# Top.net
KiCad netlist of a schematic drawn in EAGLE
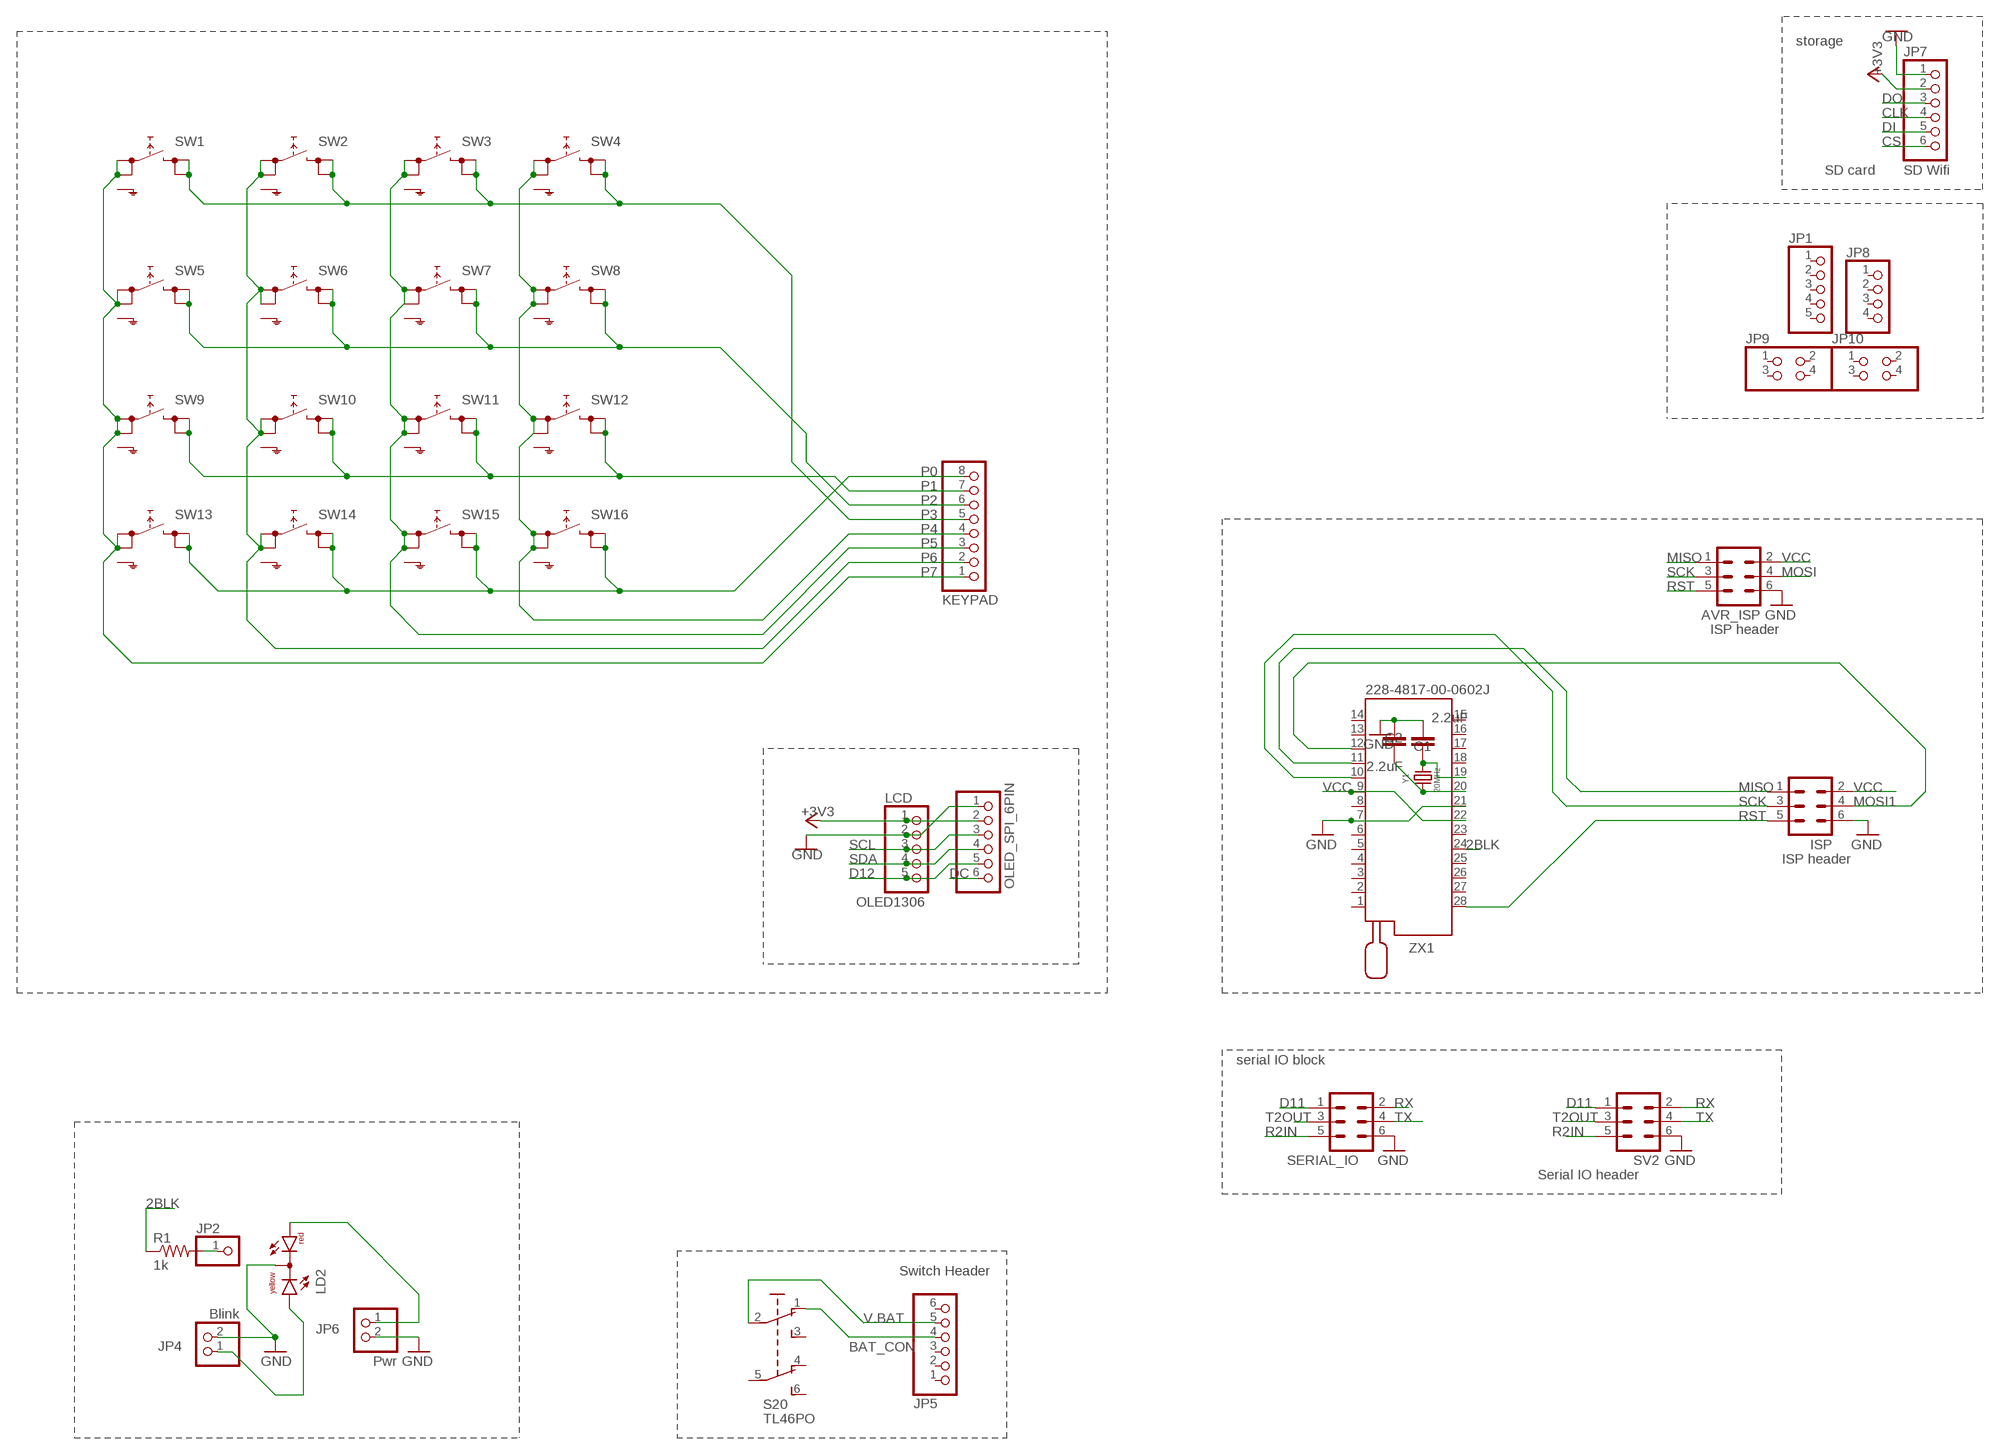
[diagram p0: schematic, sheet 1]

(export (version "E")
  (design (tool "Eeschema 10.0.6"))
  (components
    (comp (ref "AVR_ISP")
      (value "ML6")
      (footprint "eagle-import:ML6")
      (libsource (lib "eagle-import") (part "ML6"))
    )
    (comp (ref "C1")
      (value "2.2uF")
      (footprint "eagle-import:1206")
      (libsource (lib "eagle-import") (part "2.2UF-1206-50V-10%"))
    )
    (comp (ref "C2")
      (value "2.2uF")
      (footprint "eagle-import:1206")
      (libsource (lib "eagle-import") (part "2.2UF-1206-50V-10%"))
    )
    (comp (ref "ISP")
      (value "ML6")
      (footprint "eagle-import:ML6")
      (libsource (lib "eagle-import") (part "ML6"))
    )
    (comp (ref "JP1")
      (value "PINHD-1X5")
      (footprint "eagle-import:1X05")
      (libsource (lib "eagle-import") (part "PINHD-1X5"))
    )
    (comp (ref "JP2")
      (value "PINHD-1X1")
      (footprint "eagle-import:1X01")
      (libsource (lib "eagle-import") (part "PINHD-1X1"))
    )
    (comp (ref "JP4")
      (value "Blink")
      (footprint "eagle-import:1X02")
      (libsource (lib "eagle-import") (part "PINHD-1X2"))
    )
    (comp (ref "JP5")
      (value "Switch Header")
      (footprint "eagle-import:1X06")
      (libsource (lib "eagle-import") (part "pinhead_325_PINHD-1X6"))
    )
    (comp (ref "JP6")
      (value "Pwr")
      (footprint "eagle-import:1X02")
      (libsource (lib "eagle-import") (part "PINHD-1X2"))
    )
    (comp (ref "JP7")
      (value "SD Wifi")
      (footprint "eagle-import:1X06")
      (libsource (lib "eagle-import") (part "pinhead_325_PINHD-1X6"))
    )
    (comp (ref "JP8")
      (value "PINHD-1X4")
      (footprint "eagle-import:1X04")
      (libsource (lib "eagle-import") (part "PINHD-1X4"))
    )
    (comp (ref "JP9")
      (value "PINHD-2X2")
      (footprint "eagle-import:2X02")
      (libsource (lib "eagle-import") (part "PINHD-2X2"))
    )
    (comp (ref "JP10")
      (value "PINHD-2X2")
      (footprint "eagle-import:2X02")
      (libsource (lib "eagle-import") (part "PINHD-2X2"))
    )
    (comp (ref "KEYPAD")
      (value "PINHD-1X8")
      (footprint "eagle-import:1X08")
      (libsource (lib "eagle-import") (part "PINHD-1X8"))
    )
    (comp (ref "LCD")
      (value "OLED1306")
      (footprint "eagle-import:1X05")
      (libsource (lib "eagle-import") (part "PINHD-1X5"))
    )
    (comp (ref "LD2")
      (value "DUOLED-RY-C")
      (footprint "eagle-import:DUOLED-C-5MM")
      (libsource (lib "eagle-import") (part "DUOLED-RY-C"))
    )
    (comp (ref "OLED_SPI_6PIN")
      (value "PINHD-1X6")
      (footprint "eagle-import:1X06")
      (libsource (lib "eagle-import") (part "PINHD-1X6"))
    )
    (comp (ref "R1")
      (value "1k")
      (footprint "eagle-import:M1206")
      (libsource (lib "eagle-import") (part "R-US_M1206"))
    )
    (comp (ref "S20")
      (value "TL46PO")
      (footprint "eagle-import:TL4XPO")
      (libsource (lib "eagle-import") (part "TL46PO"))
    )
    (comp (ref "SERIAL_IO")
      (value "ML6")
      (footprint "eagle-import:ML6")
      (libsource (lib "eagle-import") (part "ML6"))
    )
    (comp (ref "SV2")
      (value "ML6")
      (footprint "eagle-import:ML6")
      (libsource (lib "eagle-import") (part "ML6"))
    )
    (comp (ref "SW1")
      (value "SKHMPSE010")
      (footprint "eagle-import:SKHMPXE010")
      (libsource (lib "eagle-import") (part "SKHMPE010S"))
    )
    (comp (ref "SW2")
      (value "SKHMPSE010")
      (footprint "eagle-import:SKHMPXE010")
      (libsource (lib "eagle-import") (part "SKHMPE010S"))
    )
    (comp (ref "SW3")
      (value "SKHMPSE010")
      (footprint "eagle-import:SKHMPXE010")
      (libsource (lib "eagle-import") (part "SKHMPE010S"))
    )
    (comp (ref "SW4")
      (value "SKHMPSE010")
      (footprint "eagle-import:SKHMPXE010")
      (libsource (lib "eagle-import") (part "SKHMPE010S"))
    )
    (comp (ref "SW5")
      (value "SKHMPSE010")
      (footprint "eagle-import:SKHMPXE010")
      (libsource (lib "eagle-import") (part "SKHMPE010S"))
    )
    (comp (ref "SW6")
      (value "SKHMPSE010")
      (footprint "eagle-import:SKHMPXE010")
      (libsource (lib "eagle-import") (part "SKHMPE010S"))
    )
    (comp (ref "SW7")
      (value "SKHMPSE010")
      (footprint "eagle-import:SKHMPXE010")
      (libsource (lib "eagle-import") (part "SKHMPE010S"))
    )
    (comp (ref "SW8")
      (value "SKHMPSE010")
      (footprint "eagle-import:SKHMPXE010")
      (libsource (lib "eagle-import") (part "SKHMPE010S"))
    )
    (comp (ref "SW9")
      (value "SKHMPSE010")
      (footprint "eagle-import:SKHMPXE010")
      (libsource (lib "eagle-import") (part "SKHMPE010S"))
    )
    (comp (ref "SW10")
      (value "SKHMPSE010")
      (footprint "eagle-import:SKHMPXE010")
      (libsource (lib "eagle-import") (part "SKHMPE010S"))
    )
    (comp (ref "SW11")
      (value "SKHMPSE010")
      (footprint "eagle-import:SKHMPXE010")
      (libsource (lib "eagle-import") (part "SKHMPE010S"))
    )
    (comp (ref "SW12")
      (value "SKHMPSE010")
      (footprint "eagle-import:SKHMPXE010")
      (libsource (lib "eagle-import") (part "SKHMPE010S"))
    )
    (comp (ref "SW13")
      (value "SKHMPSE010")
      (footprint "eagle-import:SKHMPXE010")
      (libsource (lib "eagle-import") (part "SKHMPE010S"))
    )
    (comp (ref "SW14")
      (value "SKHMPSE010")
      (footprint "eagle-import:SKHMPXE010")
      (libsource (lib "eagle-import") (part "SKHMPE010S"))
    )
    (comp (ref "SW15")
      (value "SKHMPSE010")
      (footprint "eagle-import:SKHMPXE010")
      (libsource (lib "eagle-import") (part "SKHMPE010S"))
    )
    (comp (ref "SW16")
      (value "SKHMPSE010")
      (footprint "eagle-import:SKHMPXE010")
      (libsource (lib "eagle-import") (part "SKHMPE010S"))
    )
    (comp (ref "Y1")
      (value "20MHz")
      (footprint "eagle-import:WE-XTAL_HC49_4HSMX")
      (fields (field (name "TOLERANCE") "±10ppm"))
      (libsource (lib "eagle-import") (part "WE-XTAL_HC49/4HSMX_830061856"))
    )
    (comp (ref "ZX1")
      (value "228-4817-00-0602J")
      (footprint "eagle-import:228-4817-00-0602J")
      (fields (field (name "MF") "3M"))
      (libsource (lib "eagle-import") (part "228-?00-0602J4817-"))
    )
  )
  (nets
    (net (code "1") (name "+3V3") (class "Default")
      (node (ref "JP7") (pin "2") (pinfunction "2_2") (pintype "passive"))
      (node (ref "LCD") (pin "1") (pinfunction "1_1") (pintype "passive"))
      (node (ref "OLED_SPI_6PIN") (pin "2") (pinfunction "2_2") (pintype "passive"))
    )
    (net (code "2") (name "/2BLK") (class "Default")
      (node (ref "R1") (pin "1") (pinfunction "1_1") (pintype "passive"))
      (node (ref "ZX1") (pin "24") (pinfunction "24_24") (pintype "passive"))
    )
    (net (code "3") (name "/BAT_CON") (class "Default")
      (node (ref "JP5") (pin "4") (pinfunction "4_4") (pintype "passive"))
      (node (ref "S20") (pin "1") (pinfunction "O_1") (pintype "passive"))
    )
    (net (code "4") (name "/CLK") (class "Default")
      (node (ref "JP7") (pin "4") (pinfunction "4_4") (pintype "passive"))
    )
    (net (code "5") (name "/CS") (class "Default")
      (node (ref "JP7") (pin "6") (pinfunction "6_6") (pintype "passive"))
    )
    (net (code "6") (name "/D11") (class "Default")
      (node (ref "SERIAL_IO") (pin "1") (pinfunction "1_1") (pintype "passive"))
      (node (ref "SV2") (pin "1") (pinfunction "1_1") (pintype "passive"))
    )
    (net (code "7") (name "/D12") (class "Default")
      (node (ref "LCD") (pin "5") (pinfunction "5_5") (pintype "passive"))
      (node (ref "OLED_SPI_6PIN") (pin "5") (pinfunction "5_5") (pintype "passive"))
    )
    (net (code "8") (name "/DC") (class "Default")
      (node (ref "OLED_SPI_6PIN") (pin "6") (pinfunction "6_6") (pintype "passive"))
    )
    (net (code "9") (name "/DI") (class "Default")
      (node (ref "JP7") (pin "5") (pinfunction "5_5") (pintype "passive"))
    )
    (net (code "10") (name "/DO") (class "Default")
      (node (ref "JP7") (pin "3") (pinfunction "3_3") (pintype "passive"))
    )
    (net (code "11") (name "/MISO") (class "Default")
      (node (ref "AVR_ISP") (pin "1") (pinfunction "1_1") (pintype "passive"))
      (node (ref "ISP") (pin "1") (pinfunction "1_1") (pintype "passive"))
      (node (ref "ZX1") (pin "11") (pinfunction "11_11") (pintype "passive"))
    )
    (net (code "12") (name "/MOSI") (class "Default")
      (node (ref "AVR_ISP") (pin "4") (pinfunction "4_4") (pintype "passive"))
    )
    (net (code "13") (name "/MOSI1") (class "Default")
      (node (ref "ISP") (pin "4") (pinfunction "4_4") (pintype "passive"))
      (node (ref "ZX1") (pin "12") (pinfunction "12_12") (pintype "passive"))
    )
    (net (code "14") (name "/P0") (class "Default")
      (node (ref "KEYPAD") (pin "8") (pinfunction "8_8") (pintype "passive"))
      (node (ref "SW13") (pin "3") (pinfunction "2.1_3") (pintype "passive"))
      (node (ref "SW13") (pin "4") (pinfunction "2.2_4") (pintype "passive"))
      (node (ref "SW14") (pin "3") (pinfunction "2.1_3") (pintype "passive"))
      (node (ref "SW14") (pin "4") (pinfunction "2.2_4") (pintype "passive"))
      (node (ref "SW15") (pin "3") (pinfunction "2.1_3") (pintype "passive"))
      (node (ref "SW15") (pin "4") (pinfunction "2.2_4") (pintype "passive"))
      (node (ref "SW16") (pin "3") (pinfunction "2.1_3") (pintype "passive"))
      (node (ref "SW16") (pin "4") (pinfunction "2.2_4") (pintype "passive"))
    )
    (net (code "15") (name "/P1") (class "Default")
      (node (ref "KEYPAD") (pin "7") (pinfunction "7_7") (pintype "passive"))
      (node (ref "SW10") (pin "3") (pinfunction "2.1_3") (pintype "passive"))
      (node (ref "SW10") (pin "4") (pinfunction "2.2_4") (pintype "passive"))
      (node (ref "SW11") (pin "3") (pinfunction "2.1_3") (pintype "passive"))
      (node (ref "SW11") (pin "4") (pinfunction "2.2_4") (pintype "passive"))
      (node (ref "SW12") (pin "3") (pinfunction "2.1_3") (pintype "passive"))
      (node (ref "SW12") (pin "4") (pinfunction "2.2_4") (pintype "passive"))
      (node (ref "SW9") (pin "3") (pinfunction "2.1_3") (pintype "passive"))
      (node (ref "SW9") (pin "4") (pinfunction "2.2_4") (pintype "passive"))
    )
    (net (code "16") (name "/P2") (class "Default")
      (node (ref "KEYPAD") (pin "6") (pinfunction "6_6") (pintype "passive"))
      (node (ref "SW5") (pin "3") (pinfunction "2.1_3") (pintype "passive"))
      (node (ref "SW5") (pin "4") (pinfunction "2.2_4") (pintype "passive"))
      (node (ref "SW6") (pin "3") (pinfunction "2.1_3") (pintype "passive"))
      (node (ref "SW6") (pin "4") (pinfunction "2.2_4") (pintype "passive"))
      (node (ref "SW7") (pin "3") (pinfunction "2.1_3") (pintype "passive"))
      (node (ref "SW7") (pin "4") (pinfunction "2.2_4") (pintype "passive"))
      (node (ref "SW8") (pin "3") (pinfunction "2.1_3") (pintype "passive"))
      (node (ref "SW8") (pin "4") (pinfunction "2.2_4") (pintype "passive"))
    )
    (net (code "17") (name "/P3") (class "Default")
      (node (ref "KEYPAD") (pin "5") (pinfunction "5_5") (pintype "passive"))
      (node (ref "SW1") (pin "3") (pinfunction "2.1_3") (pintype "passive"))
      (node (ref "SW1") (pin "4") (pinfunction "2.2_4") (pintype "passive"))
      (node (ref "SW2") (pin "3") (pinfunction "2.1_3") (pintype "passive"))
      (node (ref "SW2") (pin "4") (pinfunction "2.2_4") (pintype "passive"))
      (node (ref "SW3") (pin "3") (pinfunction "2.1_3") (pintype "passive"))
      (node (ref "SW3") (pin "4") (pinfunction "2.2_4") (pintype "passive"))
      (node (ref "SW4") (pin "3") (pinfunction "2.1_3") (pintype "passive"))
      (node (ref "SW4") (pin "4") (pinfunction "2.2_4") (pintype "passive"))
    )
    (net (code "18") (name "/P4") (class "Default")
      (node (ref "KEYPAD") (pin "4") (pinfunction "4_4") (pintype "passive"))
      (node (ref "SW12") (pin "1") (pinfunction "1.1_1") (pintype "passive"))
      (node (ref "SW12") (pin "2") (pinfunction "1.2_2") (pintype "passive"))
      (node (ref "SW16") (pin "1") (pinfunction "1.1_1") (pintype "passive"))
      (node (ref "SW16") (pin "2") (pinfunction "1.2_2") (pintype "passive"))
      (node (ref "SW4") (pin "1") (pinfunction "1.1_1") (pintype "passive"))
      (node (ref "SW4") (pin "2") (pinfunction "1.2_2") (pintype "passive"))
      (node (ref "SW8") (pin "1") (pinfunction "1.1_1") (pintype "passive"))
      (node (ref "SW8") (pin "2") (pinfunction "1.2_2") (pintype "passive"))
    )
    (net (code "19") (name "/P5") (class "Default")
      (node (ref "KEYPAD") (pin "3") (pinfunction "3_3") (pintype "passive"))
      (node (ref "SW11") (pin "1") (pinfunction "1.1_1") (pintype "passive"))
      (node (ref "SW11") (pin "2") (pinfunction "1.2_2") (pintype "passive"))
      (node (ref "SW15") (pin "1") (pinfunction "1.1_1") (pintype "passive"))
      (node (ref "SW15") (pin "2") (pinfunction "1.2_2") (pintype "passive"))
      (node (ref "SW3") (pin "1") (pinfunction "1.1_1") (pintype "passive"))
      (node (ref "SW3") (pin "2") (pinfunction "1.2_2") (pintype "passive"))
      (node (ref "SW7") (pin "1") (pinfunction "1.1_1") (pintype "passive"))
      (node (ref "SW7") (pin "2") (pinfunction "1.2_2") (pintype "passive"))
    )
    (net (code "20") (name "/P6") (class "Default")
      (node (ref "KEYPAD") (pin "2") (pinfunction "2_2") (pintype "passive"))
      (node (ref "SW10") (pin "1") (pinfunction "1.1_1") (pintype "passive"))
      (node (ref "SW10") (pin "2") (pinfunction "1.2_2") (pintype "passive"))
      (node (ref "SW14") (pin "1") (pinfunction "1.1_1") (pintype "passive"))
      (node (ref "SW14") (pin "2") (pinfunction "1.2_2") (pintype "passive"))
      (node (ref "SW2") (pin "1") (pinfunction "1.1_1") (pintype "passive"))
      (node (ref "SW2") (pin "2") (pinfunction "1.2_2") (pintype "passive"))
      (node (ref "SW6") (pin "1") (pinfunction "1.1_1") (pintype "passive"))
      (node (ref "SW6") (pin "2") (pinfunction "1.2_2") (pintype "passive"))
    )
    (net (code "21") (name "/P7") (class "Default")
      (node (ref "KEYPAD") (pin "1") (pinfunction "1_1") (pintype "passive"))
      (node (ref "SW1") (pin "1") (pinfunction "1.1_1") (pintype "passive"))
      (node (ref "SW1") (pin "2") (pinfunction "1.2_2") (pintype "passive"))
      (node (ref "SW13") (pin "1") (pinfunction "1.1_1") (pintype "passive"))
      (node (ref "SW13") (pin "2") (pinfunction "1.2_2") (pintype "passive"))
      (node (ref "SW5") (pin "1") (pinfunction "1.1_1") (pintype "passive"))
      (node (ref "SW5") (pin "2") (pinfunction "1.2_2") (pintype "passive"))
      (node (ref "SW9") (pin "1") (pinfunction "1.1_1") (pintype "passive"))
      (node (ref "SW9") (pin "2") (pinfunction "1.2_2") (pintype "passive"))
    )
    (net (code "22") (name "/R2IN") (class "Default")
      (node (ref "SERIAL_IO") (pin "5") (pinfunction "5_5") (pintype "passive"))
      (node (ref "SV2") (pin "5") (pinfunction "5_5") (pintype "passive"))
    )
    (net (code "23") (name "/RST") (class "Default")
      (node (ref "AVR_ISP") (pin "5") (pinfunction "5_5") (pintype "passive"))
      (node (ref "ISP") (pin "5") (pinfunction "5_5") (pintype "passive"))
      (node (ref "ZX1") (pin "28") (pinfunction "28_28") (pintype "passive"))
    )
    (net (code "24") (name "/RX") (class "Default")
      (node (ref "SERIAL_IO") (pin "2") (pinfunction "2_2") (pintype "passive"))
      (node (ref "SV2") (pin "2") (pinfunction "2_2") (pintype "passive"))
    )
    (net (code "25") (name "/SCK") (class "Default")
      (node (ref "AVR_ISP") (pin "3") (pinfunction "3_3") (pintype "passive"))
      (node (ref "ISP") (pin "3") (pinfunction "3_3") (pintype "passive"))
      (node (ref "ZX1") (pin "10") (pinfunction "10_10") (pintype "passive"))
    )
    (net (code "26") (name "/SCL") (class "Default")
      (node (ref "LCD") (pin "3") (pinfunction "3_3") (pintype "passive"))
      (node (ref "OLED_SPI_6PIN") (pin "3") (pinfunction "3_3") (pintype "passive"))
    )
    (net (code "27") (name "/SDA") (class "Default")
      (node (ref "LCD") (pin "4") (pinfunction "4_4") (pintype "passive"))
      (node (ref "OLED_SPI_6PIN") (pin "4") (pinfunction "4_4") (pintype "passive"))
    )
    (net (code "28") (name "/T2OUT") (class "Default")
      (node (ref "SERIAL_IO") (pin "3") (pinfunction "3_3") (pintype "passive"))
      (node (ref "SV2") (pin "3") (pinfunction "3_3") (pintype "passive"))
    )
    (net (code "29") (name "/TX") (class "Default")
      (node (ref "SERIAL_IO") (pin "4") (pinfunction "4_4") (pintype "passive"))
      (node (ref "SV2") (pin "4") (pinfunction "4_4") (pintype "passive"))
    )
    (net (code "30") (name "/V.BAT") (class "Default")
      (node (ref "JP5") (pin "5") (pinfunction "5_5") (pintype "passive"))
      (node (ref "S20") (pin "2") (pinfunction "P_2") (pintype "passive"))
    )
    (net (code "31") (name "/VCC") (class "Default")
      (node (ref "AVR_ISP") (pin "2") (pinfunction "2_2") (pintype "passive"))
      (node (ref "ISP") (pin "2") (pinfunction "2_2") (pintype "passive"))
      (node (ref "ZX1") (pin "22") (pinfunction "22_22") (pintype "passive"))
      (node (ref "ZX1") (pin "9") (pinfunction "9_9") (pintype "passive"))
    )
    (net (code "32") (name "GND") (class "Default")
      (node (ref "AVR_ISP") (pin "6") (pinfunction "6_6") (pintype "passive"))
      (node (ref "C1") (pin "2") (pinfunction "2_2") (pintype "passive"))
      (node (ref "C2") (pin "1") (pinfunction "1_1") (pintype "passive"))
      (node (ref "ISP") (pin "6") (pinfunction "6_6") (pintype "passive"))
      (node (ref "JP4") (pin "2") (pinfunction "2_2") (pintype "passive"))
      (node (ref "JP6") (pin "2") (pinfunction "2_2") (pintype "passive"))
      (node (ref "JP7") (pin "1") (pinfunction "1_1") (pintype "passive"))
      (node (ref "LCD") (pin "2") (pinfunction "2_2") (pintype "passive"))
      (node (ref "LD2") (pin "C") (pinfunction "C_C") (pintype "passive"))
      (node (ref "OLED_SPI_6PIN") (pin "1") (pinfunction "1_1") (pintype "passive"))
      (node (ref "SERIAL_IO") (pin "6") (pinfunction "6_6") (pintype "passive"))
      (node (ref "SV2") (pin "6") (pinfunction "6_6") (pintype "passive"))
      (node (ref "ZX1") (pin "21") (pinfunction "21_21") (pintype "passive"))
      (node (ref "ZX1") (pin "7") (pinfunction "7_7") (pintype "passive"))
    )
    (net (code "33") (name "Net-(C1-Pad1)") (class "Default")
      (node (ref "C1") (pin "1") (pinfunction "1_1") (pintype "passive"))
      (node (ref "Y1") (pin "2") (pinfunction "2_2") (pintype "passive"))
      (node (ref "ZX1") (pin "19") (pinfunction "19_19") (pintype "passive"))
    )
    (net (code "34") (name "Net-(C2-Pad2)") (class "Default")
      (node (ref "C2") (pin "2") (pinfunction "2_2") (pintype "passive"))
      (node (ref "Y1") (pin "1") (pinfunction "1_1") (pintype "passive"))
      (node (ref "ZX1") (pin "20") (pinfunction "20_20") (pintype "passive"))
    )
    (net (code "35") (name "Net-(JP2-Pad1)") (class "Default")
      (node (ref "JP2") (pin "1") (pinfunction "1_1") (pintype "passive"))
      (node (ref "R1") (pin "2") (pinfunction "2_2") (pintype "passive"))
    )
    (net (code "36") (name "Net-(JP6-Pad1)") (class "Default")
      (node (ref "JP6") (pin "1") (pinfunction "1_1") (pintype "passive"))
      (node (ref "LD2") (pin "AR") (pinfunction "AR_AR") (pintype "passive"))
    )
    (net (code "37") (name "Net-(LD2-AY)") (class "Default")
      (node (ref "JP4") (pin "1") (pinfunction "1_1") (pintype "passive"))
      (node (ref "LD2") (pin "AX") (pinfunction "AY_AX") (pintype "passive"))
    )
    (net (code "38") (name "unconnected-(JP1-Pad1)") (class "Default")
      (node (ref "JP1") (pin "1") (pinfunction "1_1") (pintype "passive"))
    )
    (net (code "39") (name "unconnected-(JP1-Pad2)") (class "Default")
      (node (ref "JP1") (pin "2") (pinfunction "2_2") (pintype "passive"))
    )
    (net (code "40") (name "unconnected-(JP1-Pad3)") (class "Default")
      (node (ref "JP1") (pin "3") (pinfunction "3_3") (pintype "passive"))
    )
    (net (code "41") (name "unconnected-(JP1-Pad4)") (class "Default")
      (node (ref "JP1") (pin "4") (pinfunction "4_4") (pintype "passive"))
    )
    (net (code "42") (name "unconnected-(JP1-Pad5)") (class "Default")
      (node (ref "JP1") (pin "5") (pinfunction "5_5") (pintype "passive"))
    )
    (net (code "43") (name "unconnected-(JP5-Pad1)") (class "Default")
      (node (ref "JP5") (pin "1") (pinfunction "1_1") (pintype "passive"))
    )
    (net (code "44") (name "unconnected-(JP5-Pad2)") (class "Default")
      (node (ref "JP5") (pin "2") (pinfunction "2_2") (pintype "passive"))
    )
    (net (code "45") (name "unconnected-(JP5-Pad3)") (class "Default")
      (node (ref "JP5") (pin "3") (pinfunction "3_3") (pintype "passive"))
    )
    (net (code "46") (name "unconnected-(JP5-Pad6)") (class "Default")
      (node (ref "JP5") (pin "6") (pinfunction "6_6") (pintype "passive"))
    )
    (net (code "47") (name "unconnected-(JP8-Pad1)") (class "Default")
      (node (ref "JP8") (pin "1") (pinfunction "1_1") (pintype "passive"))
    )
    (net (code "48") (name "unconnected-(JP8-Pad2)") (class "Default")
      (node (ref "JP8") (pin "2") (pinfunction "2_2") (pintype "passive"))
    )
    (net (code "49") (name "unconnected-(JP8-Pad3)") (class "Default")
      (node (ref "JP8") (pin "3") (pinfunction "3_3") (pintype "passive"))
    )
    (net (code "50") (name "unconnected-(JP8-Pad4)") (class "Default")
      (node (ref "JP8") (pin "4") (pinfunction "4_4") (pintype "passive"))
    )
    (net (code "51") (name "unconnected-(JP9-Pad1)") (class "Default")
      (node (ref "JP9") (pin "1") (pinfunction "1_1") (pintype "passive"))
    )
    (net (code "52") (name "unconnected-(JP9-Pad2)") (class "Default")
      (node (ref "JP9") (pin "2") (pinfunction "2_2") (pintype "passive"))
    )
    (net (code "53") (name "unconnected-(JP9-Pad3)") (class "Default")
      (node (ref "JP9") (pin "3") (pinfunction "3_3") (pintype "passive"))
    )
    (net (code "54") (name "unconnected-(JP9-Pad4)") (class "Default")
      (node (ref "JP9") (pin "4") (pinfunction "4_4") (pintype "passive"))
    )
    (net (code "55") (name "unconnected-(JP10-Pad1)") (class "Default")
      (node (ref "JP10") (pin "1") (pinfunction "1_1") (pintype "passive"))
    )
    (net (code "56") (name "unconnected-(JP10-Pad2)") (class "Default")
      (node (ref "JP10") (pin "2") (pinfunction "2_2") (pintype "passive"))
    )
    (net (code "57") (name "unconnected-(JP10-Pad3)") (class "Default")
      (node (ref "JP10") (pin "3") (pinfunction "3_3") (pintype "passive"))
    )
    (net (code "58") (name "unconnected-(JP10-Pad4)") (class "Default")
      (node (ref "JP10") (pin "4") (pinfunction "4_4") (pintype "passive"))
    )
    (net (code "59") (name "unconnected-(S20-O1-Pad4)") (class "Default")
      (node (ref "S20") (pin "4") (pinfunction "O1_4") (pintype "passive"))
    )
    (net (code "60") (name "unconnected-(S20-P1-Pad5)") (class "Default")
      (node (ref "S20") (pin "5") (pinfunction "P1_5") (pintype "passive"))
    )
    (net (code "61") (name "unconnected-(S20-S-Pad3)") (class "Default")
      (node (ref "S20") (pin "3") (pinfunction "S_3") (pintype "passive"))
    )
    (net (code "62") (name "unconnected-(S20-S1-Pad6)") (class "Default")
      (node (ref "S20") (pin "6") (pinfunction "S1_6") (pintype "passive"))
    )
    (net (code "63") (name "unconnected-(SW1-SH-Pad5)") (class "Default")
      (node (ref "SW1") (pin "5") (pinfunction "SH_5") (pintype "passive"))
    )
    (net (code "64") (name "unconnected-(SW2-SH-Pad5)") (class "Default")
      (node (ref "SW2") (pin "5") (pinfunction "SH_5") (pintype "passive"))
    )
    (net (code "65") (name "unconnected-(SW3-SH-Pad5)") (class "Default")
      (node (ref "SW3") (pin "5") (pinfunction "SH_5") (pintype "passive"))
    )
    (net (code "66") (name "unconnected-(SW4-SH-Pad5)") (class "Default")
      (node (ref "SW4") (pin "5") (pinfunction "SH_5") (pintype "passive"))
    )
    (net (code "67") (name "unconnected-(SW5-SH-Pad5)") (class "Default")
      (node (ref "SW5") (pin "5") (pinfunction "SH_5") (pintype "passive"))
    )
    (net (code "68") (name "unconnected-(SW6-SH-Pad5)") (class "Default")
      (node (ref "SW6") (pin "5") (pinfunction "SH_5") (pintype "passive"))
    )
    (net (code "69") (name "unconnected-(SW7-SH-Pad5)") (class "Default")
      (node (ref "SW7") (pin "5") (pinfunction "SH_5") (pintype "passive"))
    )
    (net (code "70") (name "unconnected-(SW8-SH-Pad5)") (class "Default")
      (node (ref "SW8") (pin "5") (pinfunction "SH_5") (pintype "passive"))
    )
    (net (code "71") (name "unconnected-(SW9-SH-Pad5)") (class "Default")
      (node (ref "SW9") (pin "5") (pinfunction "SH_5") (pintype "passive"))
    )
    (net (code "72") (name "unconnected-(SW10-SH-Pad5)") (class "Default")
      (node (ref "SW10") (pin "5") (pinfunction "SH_5") (pintype "passive"))
    )
    (net (code "73") (name "unconnected-(SW11-SH-Pad5)") (class "Default")
      (node (ref "SW11") (pin "5") (pinfunction "SH_5") (pintype "passive"))
    )
    (net (code "74") (name "unconnected-(SW12-SH-Pad5)") (class "Default")
      (node (ref "SW12") (pin "5") (pinfunction "SH_5") (pintype "passive"))
    )
    (net (code "75") (name "unconnected-(SW13-SH-Pad5)") (class "Default")
      (node (ref "SW13") (pin "5") (pinfunction "SH_5") (pintype "passive"))
    )
    (net (code "76") (name "unconnected-(SW14-SH-Pad5)") (class "Default")
      (node (ref "SW14") (pin "5") (pinfunction "SH_5") (pintype "passive"))
    )
    (net (code "77") (name "unconnected-(SW15-SH-Pad5)") (class "Default")
      (node (ref "SW15") (pin "5") (pinfunction "SH_5") (pintype "passive"))
    )
    (net (code "78") (name "unconnected-(SW16-SH-Pad5)") (class "Default")
      (node (ref "SW16") (pin "5") (pinfunction "SH_5") (pintype "passive"))
    )
    (net (code "79") (name "unconnected-(ZX1-Pad1)") (class "Default")
      (node (ref "ZX1") (pin "1") (pinfunction "1_1") (pintype "passive"))
    )
    (net (code "80") (name "unconnected-(ZX1-Pad2)") (class "Default")
      (node (ref "ZX1") (pin "2") (pinfunction "2_2") (pintype "passive"))
    )
    (net (code "81") (name "unconnected-(ZX1-Pad3)") (class "Default")
      (node (ref "ZX1") (pin "3") (pinfunction "3_3") (pintype "passive"))
    )
    (net (code "82") (name "unconnected-(ZX1-Pad4)") (class "Default")
      (node (ref "ZX1") (pin "4") (pinfunction "4_4") (pintype "passive"))
    )
    (net (code "83") (name "unconnected-(ZX1-Pad5)") (class "Default")
      (node (ref "ZX1") (pin "5") (pinfunction "5_5") (pintype "passive"))
    )
    (net (code "84") (name "unconnected-(ZX1-Pad6)") (class "Default")
      (node (ref "ZX1") (pin "6") (pinfunction "6_6") (pintype "passive"))
    )
    (net (code "85") (name "unconnected-(ZX1-Pad8)") (class "Default")
      (node (ref "ZX1") (pin "8") (pinfunction "8_8") (pintype "passive"))
    )
    (net (code "86") (name "unconnected-(ZX1-Pad13)") (class "Default")
      (node (ref "ZX1") (pin "13") (pinfunction "13_13") (pintype "passive"))
    )
    (net (code "87") (name "unconnected-(ZX1-Pad14)") (class "Default")
      (node (ref "ZX1") (pin "14") (pinfunction "14_14") (pintype "passive"))
    )
    (net (code "88") (name "unconnected-(ZX1-Pad15)") (class "Default")
      (node (ref "ZX1") (pin "15") (pinfunction "15_15") (pintype "passive"))
    )
    (net (code "89") (name "unconnected-(ZX1-Pad16)") (class "Default")
      (node (ref "ZX1") (pin "16") (pinfunction "16_16") (pintype "passive"))
    )
    (net (code "90") (name "unconnected-(ZX1-Pad17)") (class "Default")
      (node (ref "ZX1") (pin "17") (pinfunction "17_17") (pintype "passive"))
    )
    (net (code "91") (name "unconnected-(ZX1-Pad18)") (class "Default")
      (node (ref "ZX1") (pin "18") (pinfunction "18_18") (pintype "passive"))
    )
    (net (code "92") (name "unconnected-(ZX1-Pad23)") (class "Default")
      (node (ref "ZX1") (pin "23") (pinfunction "23_23") (pintype "passive"))
    )
    (net (code "93") (name "unconnected-(ZX1-Pad25)") (class "Default")
      (node (ref "ZX1") (pin "25") (pinfunction "25_25") (pintype "passive"))
    )
    (net (code "94") (name "unconnected-(ZX1-Pad26)") (class "Default")
      (node (ref "ZX1") (pin "26") (pinfunction "26_26") (pintype "passive"))
    )
    (net (code "95") (name "unconnected-(ZX1-Pad27)") (class "Default")
      (node (ref "ZX1") (pin "27") (pinfunction "27_27") (pintype "passive"))
    )
  )
)
